# RTC.net
KiCad netlist of a schematic drawn in Altium Designer
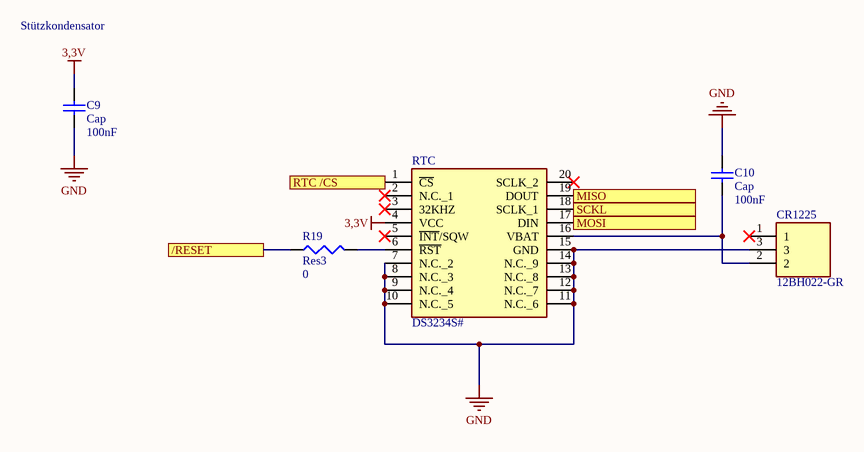
[diagram p0: RTC.SchDoc]

(export (version "E")
  (design (tool "Eeschema 10.0.6"))
  (components
    (comp (ref "C9")
      (value "Cap")
      (footprint "1608[0603]")
      (description "Capacitor")
      (fields (field (name "ALTIUM_VALUE") "100nF") (field (name "PUBLISHER") "Altium Limited"))
      (libsource (lib "Miscellaneous Devices") (part "Cap"))
    )
    (comp (ref "C10")
      (value "Cap")
      (footprint "1608[0603]")
      (description "Capacitor")
      (fields (field (name "ALTIUM_VALUE") "100nF") (field (name "PUBLISHER") "Altium Limited"))
      (libsource (lib "Miscellaneous Devices") (part "Cap"))
    )
    (comp (ref "CR1225")
      (value "12BH022-GR")
      (footprint "SamacSys:12BH022GR")
      (description "Hardware")
      (libsource (lib "*") (part "12BH022-GR"))
    )
    (comp (ref "R19")
      (value "Res3")
      (footprint "J1-0603")
      (description "Resistor")
      (fields (field (name "ALTIUM_VALUE") "0") (field (name "PUBLISHER") "Altium Limited"))
      (libsource (lib "Miscellaneous Devices") (part "Res3"))
    )
    (comp (ref "RTC")
      (value "DS3234S#")
      (footprint "SamacSys:SOIC127P1032X265-20N")
      (description "Integrated Circuit")
      (fields (field (name "MOUSER2 PART NUMBER") "700-DS3234S#"))
      (libsource (lib "SamacSys") (part "DS3234S#"))
    )
  )
  (nets
    (net (code "1") (name "/MISO") (class "Default")
      (node (ref "RTC") (pin "19") (pinfunction "DOUT_19") (pintype "passive"))
    )
    (net (code "2") (name "/MOSI") (class "Default")
      (node (ref "RTC") (pin "17") (pinfunction "DIN_17") (pintype "passive"))
    )
    (net (code "3") (name "/RTC {slash}CS") (class "Default")
      (node (ref "RTC") (pin "1") (pinfunction "~{CS}_1") (pintype "passive"))
    )
    (net (code "4") (name "/SCKL") (class "Default")
      (node (ref "RTC") (pin "18") (pinfunction "SCLK_1_18") (pintype "passive"))
    )
    (net (code "5") (name "/{slash}RESET") (class "Default")
      (node (ref "R19") (pin "1") (pinfunction "1_1") (pintype "passive"))
    )
    (net (code "6") (name "3,3V") (class "Default")
      (node (ref "C9") (pin "2") (pinfunction "2_2") (pintype "passive"))
      (node (ref "RTC") (pin "4") (pinfunction "VCC_4") (pintype "passive"))
    )
    (net (code "7") (name "GND") (class "Default")
      (node (ref "C10") (pin "2") (pinfunction "2_2") (pintype "passive"))
      (node (ref "C9") (pin "1") (pinfunction "1_1") (pintype "passive"))
      (node (ref "CR1225") (pin "3") (pinfunction "3_3") (pintype "passive"))
      (node (ref "RTC") (pin "10") (pinfunction "N.C._5_10") (pintype "passive"))
      (node (ref "RTC") (pin "11") (pinfunction "N.C._6_11") (pintype "passive"))
      (node (ref "RTC") (pin "12") (pinfunction "N.C._7_12") (pintype "passive"))
      (node (ref "RTC") (pin "13") (pinfunction "N.C._8_13") (pintype "passive"))
      (node (ref "RTC") (pin "14") (pinfunction "N.C._9_14") (pintype "passive"))
      (node (ref "RTC") (pin "15") (pinfunction "GND_15") (pintype "passive"))
      (node (ref "RTC") (pin "7") (pinfunction "N.C._2_7") (pintype "passive"))
      (node (ref "RTC") (pin "8") (pinfunction "N.C._3_8") (pintype "passive"))
      (node (ref "RTC") (pin "9") (pinfunction "N.C._4_9") (pintype "passive"))
    )
    (net (code "8") (name "Net-(RTC-VBAT)") (class "Default")
      (node (ref "C10") (pin "1") (pinfunction "1_1") (pintype "passive"))
      (node (ref "CR1225") (pin "2") (pinfunction "2_2") (pintype "passive"))
      (node (ref "RTC") (pin "16") (pinfunction "VBAT_16") (pintype "passive"))
    )
    (net (code "9") (name "Net-(RTC-~{RST})") (class "Default")
      (node (ref "R19") (pin "2") (pinfunction "2_2") (pintype "passive"))
      (node (ref "RTC") (pin "6") (pinfunction "~{RST}_6") (pintype "passive"))
    )
    (net (code "10") (name "unconnected-(CR1225-Pad1)") (class "Default")
      (node (ref "CR1225") (pin "1") (pinfunction "1_1") (pintype "passive+no_connect"))
    )
    (net (code "11") (name "unconnected-(RTC-32KHZ-Pad3)") (class "Default")
      (node (ref "RTC") (pin "3") (pinfunction "32KHZ_3") (pintype "passive+no_connect"))
    )
    (net (code "12") (name "unconnected-(RTC-N.C._1-Pad2)") (class "Default")
      (node (ref "RTC") (pin "2") (pinfunction "N.C._1_2") (pintype "passive+no_connect"))
    )
    (net (code "13") (name "unconnected-(RTC-SCLK_2-Pad20)") (class "Default")
      (node (ref "RTC") (pin "20") (pinfunction "SCLK_2_20") (pintype "passive+no_connect"))
    )
    (net (code "14") (name "unconnected-(RTC-~{INT}{slash}SQW-Pad5)") (class "Default")
      (node (ref "RTC") (pin "5") (pinfunction "~{INT}/SQW_5") (pintype "passive+no_connect"))
    )
  )
)
